# ExtremeFeedbackDevice.net
KiCad netlist of a schematic drawn in EAGLE
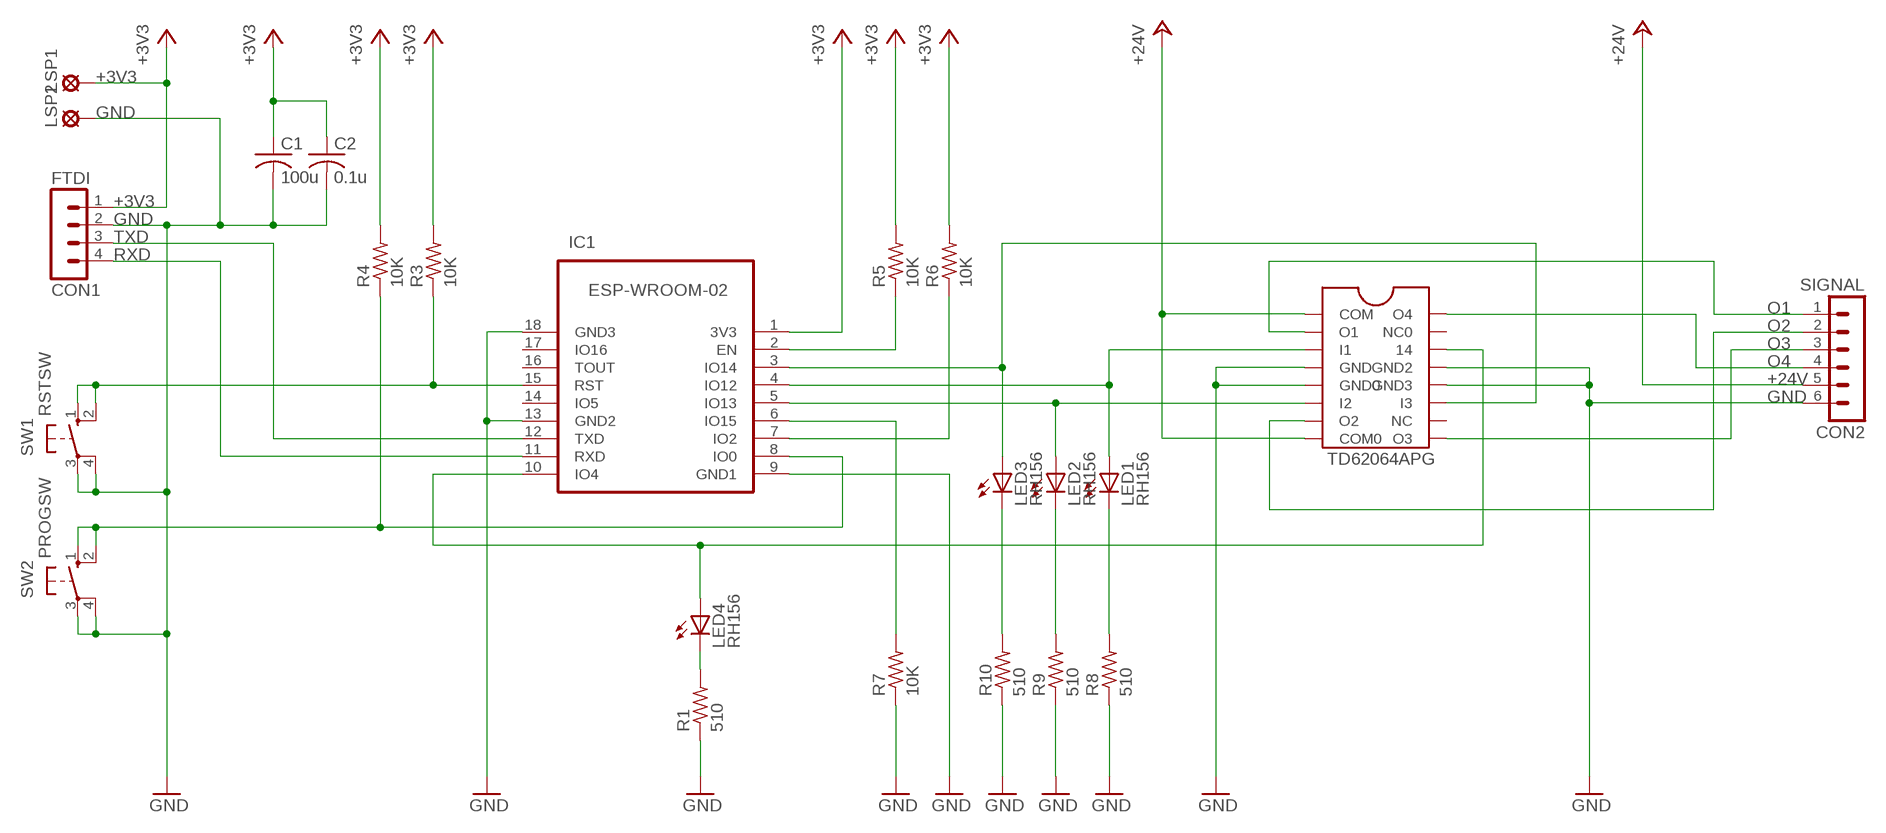
[diagram p0: schematic, sheet 1]

(export (version "E")
  (design (tool "Eeschema 10.0.6"))
  (components
    (comp (ref "C1")
      (value "100u")
      (footprint "eagle-import:C050-024X044")
      (libsource (lib "eagle-import") (part "C-US050-024X044"))
    )
    (comp (ref "C2")
      (value "0.1u")
      (footprint "eagle-import:C050-024X044")
      (libsource (lib "eagle-import") (part "C-US050-024X044"))
    )
    (comp (ref "CON1")
      (value "FTDI")
      (footprint "eagle-import:MA04-1")
      (libsource (lib "eagle-import") (part "MA04-1"))
    )
    (comp (ref "CON2")
      (value "SIGNAL")
      (footprint "eagle-import:MA06-1")
      (libsource (lib "eagle-import") (part "MA06-1"))
    )
    (comp (ref "IC1")
      (value "ESP-WROOM-02")
      (footprint "eagle-import:FRONT-FACE")
      (libsource (lib "eagle-import") (part "ESP-WROOM-02FRONT-FACE"))
    )
    (comp (ref "IC2")
      (value "IC2")
      (footprint "eagle-import:TD62064APG")
      (libsource (lib "eagle-import") (part "TD62064APG"))
    )
    (comp (ref "LED1")
      (value "RH156")
      (footprint "eagle-import:LED3MM")
      (fields (field (name "MF") "VISHAY SEMICONDUCTOR"))
      (libsource (lib "eagle-import") (part "TLLR4400"))
    )
    (comp (ref "LED2")
      (value "RH156")
      (footprint "eagle-import:LED3MM")
      (fields (field (name "MF") "VISHAY SEMICONDUCTOR"))
      (libsource (lib "eagle-import") (part "TLLR4400"))
    )
    (comp (ref "LED3")
      (value "RH156")
      (footprint "eagle-import:LED3MM")
      (fields (field (name "MF") "VISHAY SEMICONDUCTOR"))
      (libsource (lib "eagle-import") (part "TLLR4400"))
    )
    (comp (ref "LED4")
      (value "RH156")
      (footprint "eagle-import:LED3MM")
      (fields (field (name "MF") "VISHAY SEMICONDUCTOR"))
      (libsource (lib "eagle-import") (part "TLLR4400"))
    )
    (comp (ref "LSP1")
      (value "LSP10")
      (footprint "eagle-import:LSP10")
      (libsource (lib "eagle-import") (part "LSP10"))
    )
    (comp (ref "LSP2")
      (value "LSP10")
      (footprint "eagle-import:LSP10")
      (libsource (lib "eagle-import") (part "LSP10"))
    )
    (comp (ref "R1")
      (value "510")
      (footprint "eagle-import:0204_7")
      (libsource (lib "eagle-import") (part "R-US_0204/7"))
    )
    (comp (ref "R3")
      (value "10K")
      (footprint "eagle-import:0204_7")
      (libsource (lib "eagle-import") (part "R-US_0204/7"))
    )
    (comp (ref "R4")
      (value "10K")
      (footprint "eagle-import:0204_7")
      (libsource (lib "eagle-import") (part "R-US_0204/7"))
    )
    (comp (ref "R5")
      (value "10K")
      (footprint "eagle-import:0204_7")
      (libsource (lib "eagle-import") (part "R-US_0204/7"))
    )
    (comp (ref "R6")
      (value "10K")
      (footprint "eagle-import:0204_7")
      (libsource (lib "eagle-import") (part "R-US_0204/7"))
    )
    (comp (ref "R7")
      (value "10K")
      (footprint "eagle-import:0204_7")
      (libsource (lib "eagle-import") (part "R-US_0204/7"))
    )
    (comp (ref "R8")
      (value "510")
      (footprint "eagle-import:0204_7")
      (libsource (lib "eagle-import") (part "R-US_0204/7"))
    )
    (comp (ref "R9")
      (value "510")
      (footprint "eagle-import:0204_7")
      (libsource (lib "eagle-import") (part "R-US_0204/7"))
    )
    (comp (ref "R10")
      (value "510")
      (footprint "eagle-import:0204_7")
      (fields (field (name "SPICEPREFIX") "R"))
      (libsource (lib "eagle-import") (part "R-US_0204/7"))
    )
    (comp (ref "SW1")
      (value "RSTSW")
      (footprint "eagle-import:B3F-10XX")
      (fields (field (name "MPN") "B3F-1000"))
      (libsource (lib "eagle-import") (part "10-XX"))
    )
    (comp (ref "SW2")
      (value "PROGSW")
      (footprint "eagle-import:B3F-10XX")
      (fields (field (name "MPN") "B3F-1000"))
      (libsource (lib "eagle-import") (part "10-XX"))
    )
  )
  (nets
    (net (code "1") (name "+3V3") (class "Default")
      (node (ref "C1") (pin "1") (pinfunction "1_1") (pintype "passive"))
      (node (ref "C2") (pin "1") (pinfunction "1_1") (pintype "passive"))
      (node (ref "CON1") (pin "1") (pinfunction "1_1") (pintype "passive"))
      (node (ref "IC1") (pin "1") (pinfunction "3V3_1") (pintype "power_in"))
      (node (ref "LSP1") (pin "MP") (pinfunction "MP_MP") (pintype "passive"))
      (node (ref "R3") (pin "2") (pinfunction "2_2") (pintype "passive"))
      (node (ref "R4") (pin "2") (pinfunction "2_2") (pintype "passive"))
      (node (ref "R5") (pin "2") (pinfunction "2_2") (pintype "passive"))
      (node (ref "R6") (pin "2") (pinfunction "2_2") (pintype "passive"))
    )
    (net (code "2") (name "+24V") (class "Default")
      (node (ref "CON2") (pin "5") (pinfunction "5_5") (pintype "passive"))
      (node (ref "IC2") (pin "1") (pinfunction "COM_1") (pintype "passive"))
      (node (ref "IC2") (pin "8") (pinfunction "COM0_8") (pintype "passive"))
    )
    (net (code "3") (name "/O1") (class "Default")
      (node (ref "CON2") (pin "1") (pinfunction "1_1") (pintype "passive"))
      (node (ref "IC2") (pin "2") (pinfunction "O1_2") (pintype "passive"))
    )
    (net (code "4") (name "/O2") (class "Default")
      (node (ref "CON2") (pin "2") (pinfunction "2_2") (pintype "passive"))
      (node (ref "IC2") (pin "7") (pinfunction "O2_7") (pintype "passive"))
    )
    (net (code "5") (name "/O3") (class "Default")
      (node (ref "CON2") (pin "3") (pinfunction "3_3") (pintype "passive"))
      (node (ref "IC2") (pin "9") (pinfunction "O3_9") (pintype "passive"))
    )
    (net (code "6") (name "/O4") (class "Default")
      (node (ref "CON2") (pin "4") (pinfunction "4_4") (pintype "passive"))
      (node (ref "IC2") (pin "16") (pinfunction "O4_16") (pintype "passive"))
    )
    (net (code "7") (name "/RXD") (class "Default")
      (node (ref "CON1") (pin "4") (pinfunction "4_4") (pintype "passive"))
      (node (ref "IC1") (pin "11") (pinfunction "RXD_11") (pintype "bidirectional"))
    )
    (net (code "8") (name "/TXD") (class "Default")
      (node (ref "CON1") (pin "3") (pinfunction "3_3") (pintype "passive"))
      (node (ref "IC1") (pin "12") (pinfunction "TXD_12") (pintype "bidirectional"))
    )
    (net (code "9") (name "GND") (class "Default")
      (node (ref "C1") (pin "2") (pinfunction "2_2") (pintype "passive"))
      (node (ref "C2") (pin "2") (pinfunction "2_2") (pintype "passive"))
      (node (ref "CON1") (pin "2") (pinfunction "2_2") (pintype "passive"))
      (node (ref "CON2") (pin "6") (pinfunction "6_6") (pintype "passive"))
      (node (ref "IC1") (pin "13") (pinfunction "GND2_13") (pintype "power_in"))
      (node (ref "IC1") (pin "18") (pinfunction "GND3_18") (pintype "power_in"))
      (node (ref "IC1") (pin "9") (pinfunction "GND1_9") (pintype "power_in"))
      (node (ref "IC2") (pin "12") (pinfunction "GND3_12") (pintype "passive"))
      (node (ref "IC2") (pin "13") (pinfunction "GND2_13") (pintype "passive"))
      (node (ref "IC2") (pin "4") (pinfunction "GND_4") (pintype "passive"))
      (node (ref "IC2") (pin "5") (pinfunction "GND0_5") (pintype "passive"))
      (node (ref "LSP2") (pin "MP") (pinfunction "MP_MP") (pintype "passive"))
      (node (ref "R1") (pin "1") (pinfunction "1_1") (pintype "passive"))
      (node (ref "R10") (pin "1") (pinfunction "1_1") (pintype "passive"))
      (node (ref "R7") (pin "1") (pinfunction "1_1") (pintype "passive"))
      (node (ref "R8") (pin "1") (pinfunction "1_1") (pintype "passive"))
      (node (ref "R9") (pin "1") (pinfunction "1_1") (pintype "passive"))
      (node (ref "SW1") (pin "3") (pinfunction "P_3") (pintype "passive"))
      (node (ref "SW1") (pin "4") (pinfunction "P1_4") (pintype "passive"))
      (node (ref "SW2") (pin "3") (pinfunction "P_3") (pintype "passive"))
      (node (ref "SW2") (pin "4") (pinfunction "P1_4") (pintype "passive"))
    )
    (net (code "10") (name "Net-(IC1-EN)") (class "Default")
      (node (ref "IC1") (pin "2") (pinfunction "EN_2") (pintype "bidirectional"))
      (node (ref "R5") (pin "1") (pinfunction "1_1") (pintype "passive"))
    )
    (net (code "11") (name "Net-(IC1-IO0)") (class "Default")
      (node (ref "IC1") (pin "8") (pinfunction "IO0_8") (pintype "bidirectional"))
      (node (ref "R4") (pin "1") (pinfunction "1_1") (pintype "passive"))
      (node (ref "SW2") (pin "1") (pinfunction "S_1") (pintype "passive"))
      (node (ref "SW2") (pin "2") (pinfunction "S1_2") (pintype "passive"))
    )
    (net (code "12") (name "Net-(IC1-IO2)") (class "Default")
      (node (ref "IC1") (pin "7") (pinfunction "IO2_7") (pintype "bidirectional"))
      (node (ref "R6") (pin "1") (pinfunction "1_1") (pintype "passive"))
    )
    (net (code "13") (name "Net-(IC1-IO4)") (class "Default")
      (node (ref "IC1") (pin "10") (pinfunction "IO4_10") (pintype "bidirectional"))
      (node (ref "IC2") (pin "14") (pinfunction "14_14") (pintype "passive"))
      (node (ref "LED4") (pin "A") (pinfunction "A_A") (pintype "passive"))
    )
    (net (code "14") (name "Net-(IC1-IO12)") (class "Default")
      (node (ref "IC1") (pin "4") (pinfunction "IO12_4") (pintype "bidirectional"))
      (node (ref "IC2") (pin "3") (pinfunction "I1_3") (pintype "passive"))
      (node (ref "LED1") (pin "A") (pinfunction "A_A") (pintype "passive"))
    )
    (net (code "15") (name "Net-(IC1-IO13)") (class "Default")
      (node (ref "IC1") (pin "5") (pinfunction "IO13_5") (pintype "bidirectional"))
      (node (ref "IC2") (pin "6") (pinfunction "I2_6") (pintype "passive"))
      (node (ref "LED2") (pin "A") (pinfunction "A_A") (pintype "passive"))
    )
    (net (code "16") (name "Net-(IC1-IO14)") (class "Default")
      (node (ref "IC1") (pin "3") (pinfunction "IO14_3") (pintype "bidirectional"))
      (node (ref "IC2") (pin "11") (pinfunction "I3_11") (pintype "passive"))
      (node (ref "LED3") (pin "A") (pinfunction "A_A") (pintype "passive"))
    )
    (net (code "17") (name "Net-(IC1-IO15)") (class "Default")
      (node (ref "IC1") (pin "6") (pinfunction "IO15_6") (pintype "bidirectional"))
      (node (ref "R7") (pin "2") (pinfunction "2_2") (pintype "passive"))
    )
    (net (code "18") (name "Net-(IC1-RST)") (class "Default")
      (node (ref "IC1") (pin "15") (pinfunction "RST_15") (pintype "bidirectional"))
      (node (ref "R3") (pin "1") (pinfunction "1_1") (pintype "passive"))
      (node (ref "SW1") (pin "1") (pinfunction "S_1") (pintype "passive"))
      (node (ref "SW1") (pin "2") (pinfunction "S1_2") (pintype "passive"))
    )
    (net (code "19") (name "Net-(LED1-C)") (class "Default")
      (node (ref "LED1") (pin "K") (pinfunction "C_K") (pintype "passive"))
      (node (ref "R8") (pin "2") (pinfunction "2_2") (pintype "passive"))
    )
    (net (code "20") (name "Net-(LED2-C)") (class "Default")
      (node (ref "LED2") (pin "K") (pinfunction "C_K") (pintype "passive"))
      (node (ref "R9") (pin "2") (pinfunction "2_2") (pintype "passive"))
    )
    (net (code "21") (name "Net-(LED3-C)") (class "Default")
      (node (ref "LED3") (pin "K") (pinfunction "C_K") (pintype "passive"))
      (node (ref "R10") (pin "2") (pinfunction "2_2") (pintype "passive"))
    )
    (net (code "22") (name "Net-(LED4-C)") (class "Default")
      (node (ref "LED4") (pin "K") (pinfunction "C_K") (pintype "passive"))
      (node (ref "R1") (pin "2") (pinfunction "2_2") (pintype "passive"))
    )
    (net (code "23") (name "unconnected-(IC1-IO5-Pad14)") (class "Default")
      (node (ref "IC1") (pin "14") (pinfunction "IO5_14") (pintype "open_collector"))
    )
    (net (code "24") (name "unconnected-(IC1-IO16-Pad17)") (class "Default")
      (node (ref "IC1") (pin "17") (pinfunction "IO16_17") (pintype "bidirectional"))
    )
    (net (code "25") (name "unconnected-(IC1-TOUT-Pad16)") (class "Default")
      (node (ref "IC1") (pin "16") (pinfunction "TOUT_16") (pintype "bidirectional"))
    )
    (net (code "26") (name "unconnected-(IC2-NC-Pad10)") (class "Default")
      (node (ref "IC2") (pin "10") (pinfunction "NC_10") (pintype "passive"))
    )
    (net (code "27") (name "unconnected-(IC2-NC0-Pad15)") (class "Default")
      (node (ref "IC2") (pin "15") (pinfunction "NC0_15") (pintype "passive"))
    )
  )
)
